# piggyback.net
KiCad netlist of a schematic drawn in EAGLE
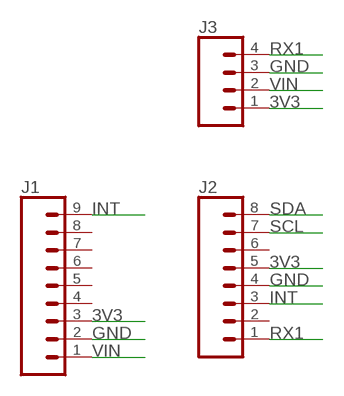
[diagram p0: schematic, sheet 1]

(export (version "E")
  (design (tool "Eeschema 10.0.6"))
  (components
    (comp (ref "J1")
      (value "CONN_09NO_SILK")
      (footprint "eagle-import:1X09_NO_SILK")
      (libsource (lib "eagle-import") (part "CONN_09NO_SILK"))
    )
    (comp (ref "J2")
      (value "CONN_08NO_SILK_FEMALE_PTH")
      (footprint "eagle-import:1X08_NO_SILK")
      (libsource (lib "eagle-import") (part "CONN_08NO_SILK_FEMALE_PTH"))
    )
    (comp (ref "J3")
      (value "CONN_041X04_NO_SILK")
      (footprint "eagle-import:1X04_NO_SILK")
      (libsource (lib "eagle-import") (part "CONN_041X04_NO_SILK"))
    )
  )
  (nets
    (net (code "1") (name "/3V3") (class "Default")
      (node (ref "J1") (pin "3") (pinfunction "3_3") (pintype "passive"))
      (node (ref "J2") (pin "5") (pinfunction "5_5") (pintype "passive"))
      (node (ref "J3") (pin "1") (pinfunction "1_1") (pintype "passive"))
    )
    (net (code "2") (name "/GND") (class "Default")
      (node (ref "J1") (pin "2") (pinfunction "2_2") (pintype "passive"))
      (node (ref "J2") (pin "4") (pinfunction "4_4") (pintype "passive"))
      (node (ref "J3") (pin "3") (pinfunction "3_3") (pintype "passive"))
    )
    (net (code "3") (name "/INT") (class "Default")
      (node (ref "J1") (pin "9") (pinfunction "9_9") (pintype "passive"))
      (node (ref "J2") (pin "3") (pinfunction "3_3") (pintype "passive"))
    )
    (net (code "4") (name "/RX1") (class "Default")
      (node (ref "J2") (pin "1") (pinfunction "1_1") (pintype "passive"))
      (node (ref "J3") (pin "4") (pinfunction "4_4") (pintype "passive"))
    )
    (net (code "5") (name "/SCL") (class "Default")
      (node (ref "J2") (pin "7") (pinfunction "7_7") (pintype "passive"))
    )
    (net (code "6") (name "/SDA") (class "Default")
      (node (ref "J2") (pin "8") (pinfunction "8_8") (pintype "passive"))
    )
    (net (code "7") (name "/VIN") (class "Default")
      (node (ref "J1") (pin "1") (pinfunction "1_1") (pintype "passive"))
      (node (ref "J3") (pin "2") (pinfunction "2_2") (pintype "passive"))
    )
    (net (code "8") (name "unconnected-(J1-Pad4)") (class "Default")
      (node (ref "J1") (pin "4") (pinfunction "4_4") (pintype "passive"))
    )
    (net (code "9") (name "unconnected-(J1-Pad5)") (class "Default")
      (node (ref "J1") (pin "5") (pinfunction "5_5") (pintype "passive"))
    )
    (net (code "10") (name "unconnected-(J1-Pad6)") (class "Default")
      (node (ref "J1") (pin "6") (pinfunction "6_6") (pintype "passive"))
    )
    (net (code "11") (name "unconnected-(J1-Pad7)") (class "Default")
      (node (ref "J1") (pin "7") (pinfunction "7_7") (pintype "passive"))
    )
    (net (code "12") (name "unconnected-(J1-Pad8)") (class "Default")
      (node (ref "J1") (pin "8") (pinfunction "8_8") (pintype "passive"))
    )
    (net (code "13") (name "unconnected-(J2-Pad2)") (class "Default")
      (node (ref "J2") (pin "2") (pinfunction "2_2") (pintype "passive"))
    )
    (net (code "14") (name "unconnected-(J2-Pad6)") (class "Default")
      (node (ref "J2") (pin "6") (pinfunction "6_6") (pintype "passive"))
    )
  )
)
